# PMIC_Power.net
KiCad netlist of a schematic drawn in Altium Designer
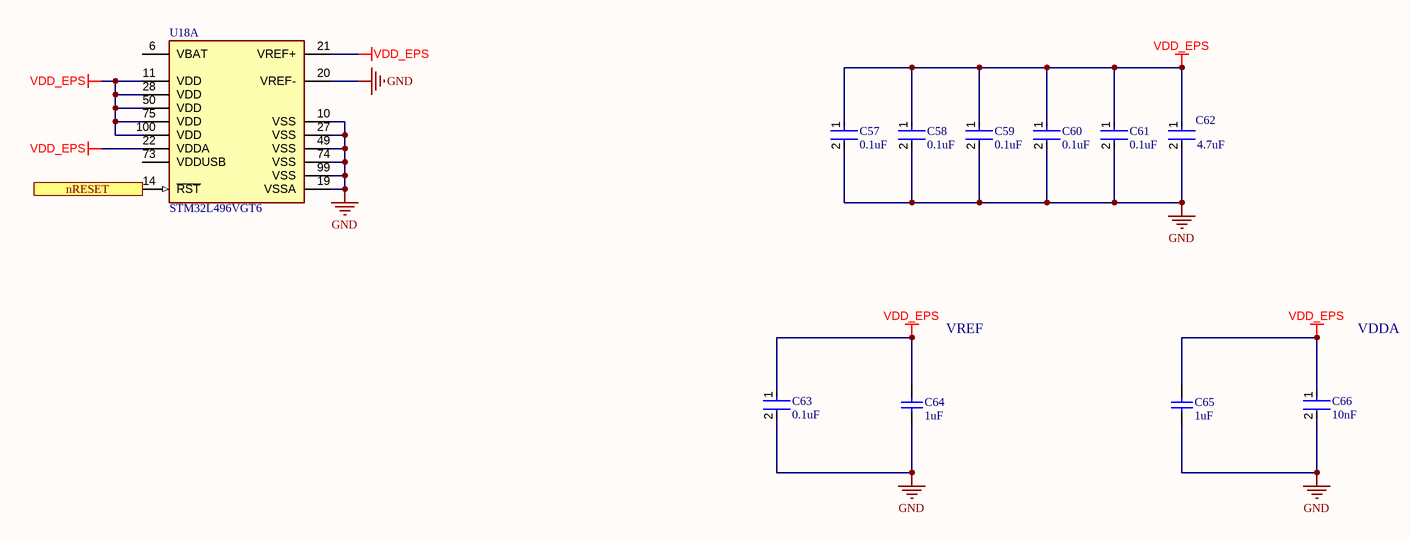
[diagram p0: PMIC_Power.SchDoc]

(export (version "E")
  (design (tool "Eeschema 10.0.6"))
  (components
    (comp (ref "C57")
      (value "0.1uF")
      (footprint "FP-C0603C-CF-MFG")
      (description "CAP CER 0.1UF 50V X7R 0603")
      (fields (field (name "TOLERANCE") "0.1") (field (name "MANUFACTURER") "KEMET"))
      (libsource (lib "Altium Content Vault") (part "b4654b650e69147ec39a6b967a45e02"))
    )
    (comp (ref "C58")
      (value "0.1uF")
      (footprint "FP-C0603C-CF-MFG")
      (description "CAP CER 0.1UF 50V X7R 0603")
      (fields (field (name "TOLERANCE") "0.1") (field (name "MANUFACTURER") "KEMET"))
      (libsource (lib "Altium Content Vault") (part "b4654b650e69147ec39a6b967a45e02"))
    )
    (comp (ref "C59")
      (value "0.1uF")
      (footprint "FP-C0603C-CF-MFG")
      (description "CAP CER 0.1UF 50V X7R 0603")
      (fields (field (name "TOLERANCE") "0.1") (field (name "MANUFACTURER") "KEMET"))
      (libsource (lib "Altium Content Vault") (part "b4654b650e69147ec39a6b967a45e02"))
    )
    (comp (ref "C60")
      (value "0.1uF")
      (footprint "FP-C0603C-CF-MFG")
      (description "CAP CER 0.1UF 50V X7R 0603")
      (fields (field (name "TOLERANCE") "0.1") (field (name "MANUFACTURER") "KEMET"))
      (libsource (lib "Altium Content Vault") (part "b4654b650e69147ec39a6b967a45e02"))
    )
    (comp (ref "C61")
      (value "0.1uF")
      (footprint "FP-C0603C-CF-MFG")
      (description "CAP CER 0.1UF 50V X7R 0603")
      (fields (field (name "TOLERANCE") "0.1") (field (name "MANUFACTURER") "KEMET"))
      (libsource (lib "Altium Content Vault") (part "b4654b650e69147ec39a6b967a45e02"))
    )
    (comp (ref "C62")
      (value "4.7uF")
      (footprint "FP-GRM188-0_15-IPC_A")
      (description "CAP CER 4.7UF 10V X7S 0603")
      (fields (field (name "TOLERANCE") "10%"))
      (libsource (lib "Altium Content Vault") (part "02cd4be3c70576c341d710602a673aa"))
    )
    (comp (ref "C63")
      (value "0.1uF")
      (footprint "FP-C0603C-CF-MFG")
      (description "CAP CER 0.1UF 50V X7R 0603")
      (fields (field (name "TOLERANCE") "0.1") (field (name "MANUFACTURER") "KEMET"))
      (libsource (lib "Altium Content Vault") (part "b4654b650e69147ec39a6b967a45e02"))
    )
    (comp (ref "C64")
      (value "1uF")
      (footprint "CAPC1608X90X35LL15T15")
      (fields (field (name "MANUFACTURER") "Kemet") (field (name "PART NUMBER") "C0603C105K4RACTU"))
      (libsource (lib "Altium Content Vault") (part "CAP"))
    )
    (comp (ref "C65")
      (value "1uF")
      (footprint "CAPC1608X90X35LL15T15")
      (fields (field (name "MANUFACTURER") "Kemet") (field (name "PART NUMBER") "C0603C105K4RACTU"))
      (libsource (lib "Altium Content Vault") (part "CAP"))
    )
    (comp (ref "C66")
      (value "10nF")
      (footprint "FP-GRM188-0_1-e0_2_0_5-IPC_A")
      (description "Chip Multilayer Ceramic Capacitors for General Purpose, 0603, 10000pF, X7R, 15%, 10%, 100V")
      (fields (field (name "VOLTAGE") "100V") (field (name "TOLERANCE") "10%"))
      (libsource (lib "Altium Content Vault") (part "11868f565c42a9108669ba33697ecf6"))
    )
    (comp (ref "U18")
      (value "STM32L496VGT6")
      (footprint "FP-LQFP100-1L-MFG")
      (description "IC MCU 32BIT 1MB FLASH 100LQFP")
      (fields
        (field (name "MANUFACTURER") "STMicroelectronics")
        (field (name "OCTOPART") "https://octopart.com/stm32l496vgt6-stmicroelectronics-80826723")
      )
      (libsource (lib "Altium Content Vault") (part "c3654b0af0513536dfc3423c68ccd0e"))
    )
  )
  (nets
    (net (code "1") (name "/nRESET") (class "Default")
      (node (ref "U18") (pin "14") (pinfunction "~{RST}_14") (pintype "input"))
    )
    (net (code "2") (name "GND") (class "Default")
      (node (ref "C57") (pin "2") (pinfunction "2_2") (pintype "passive"))
      (node (ref "C58") (pin "2") (pinfunction "2_2") (pintype "passive"))
      (node (ref "C59") (pin "2") (pinfunction "2_2") (pintype "passive"))
      (node (ref "C60") (pin "2") (pinfunction "2_2") (pintype "passive"))
      (node (ref "C61") (pin "2") (pinfunction "2_2") (pintype "passive"))
      (node (ref "C62") (pin "2") (pinfunction "2_2") (pintype "passive"))
      (node (ref "C63") (pin "2") (pinfunction "2_2") (pintype "passive"))
      (node (ref "C64") (pin "2") (pinfunction "2_2") (pintype "passive"))
      (node (ref "C65") (pin "2") (pinfunction "2_2") (pintype "passive"))
      (node (ref "C66") (pin "2") (pinfunction "2_2") (pintype "passive"))
      (node (ref "U18") (pin "10") (pinfunction "VSS_10") (pintype "power_in"))
      (node (ref "U18") (pin "19") (pinfunction "VSSA_19") (pintype "power_in"))
      (node (ref "U18") (pin "20") (pinfunction "VREF-_20") (pintype "power_in"))
      (node (ref "U18") (pin "27") (pinfunction "VSS_27") (pintype "power_in"))
      (node (ref "U18") (pin "49") (pinfunction "VSS_49") (pintype "power_in"))
      (node (ref "U18") (pin "74") (pinfunction "VSS_74") (pintype "power_in"))
      (node (ref "U18") (pin "99") (pinfunction "VSS_99") (pintype "power_in"))
    )
    (net (code "3") (name "VDD_EPS") (class "Default")
      (node (ref "C57") (pin "1") (pinfunction "1_1") (pintype "passive"))
      (node (ref "C58") (pin "1") (pinfunction "1_1") (pintype "passive"))
      (node (ref "C59") (pin "1") (pinfunction "1_1") (pintype "passive"))
      (node (ref "C60") (pin "1") (pinfunction "1_1") (pintype "passive"))
      (node (ref "C61") (pin "1") (pinfunction "1_1") (pintype "passive"))
      (node (ref "C62") (pin "1") (pinfunction "1_1") (pintype "passive"))
      (node (ref "C63") (pin "1") (pinfunction "1_1") (pintype "passive"))
      (node (ref "C64") (pin "1") (pinfunction "1_1") (pintype "passive"))
      (node (ref "C65") (pin "1") (pinfunction "1_1") (pintype "passive"))
      (node (ref "C66") (pin "1") (pinfunction "1_1") (pintype "passive"))
      (node (ref "U18") (pin "100") (pinfunction "VDD_100") (pintype "power_in"))
      (node (ref "U18") (pin "11") (pinfunction "VDD_11") (pintype "power_in"))
      (node (ref "U18") (pin "21") (pinfunction "VREF+_21") (pintype "power_in"))
      (node (ref "U18") (pin "22") (pinfunction "VDDA_22") (pintype "power_in"))
      (node (ref "U18") (pin "28") (pinfunction "VDD_28") (pintype "power_in"))
      (node (ref "U18") (pin "50") (pinfunction "VDD_50") (pintype "power_in"))
      (node (ref "U18") (pin "75") (pinfunction "VDD_75") (pintype "power_in"))
    )
    (net (code "4") (name "unconnected-(U18A-VBAT-Pad6)") (class "Default")
      (node (ref "U18") (pin "6") (pinfunction "VBAT_6") (pintype "power_in"))
    )
    (net (code "5") (name "unconnected-(U18A-VDDUSB-Pad73)") (class "Default")
      (node (ref "U18") (pin "73") (pinfunction "VDDUSB_73") (pintype "power_in"))
    )
  )
)
